# design.net
KiCad netlist of a schematic drawn in EasyEDA
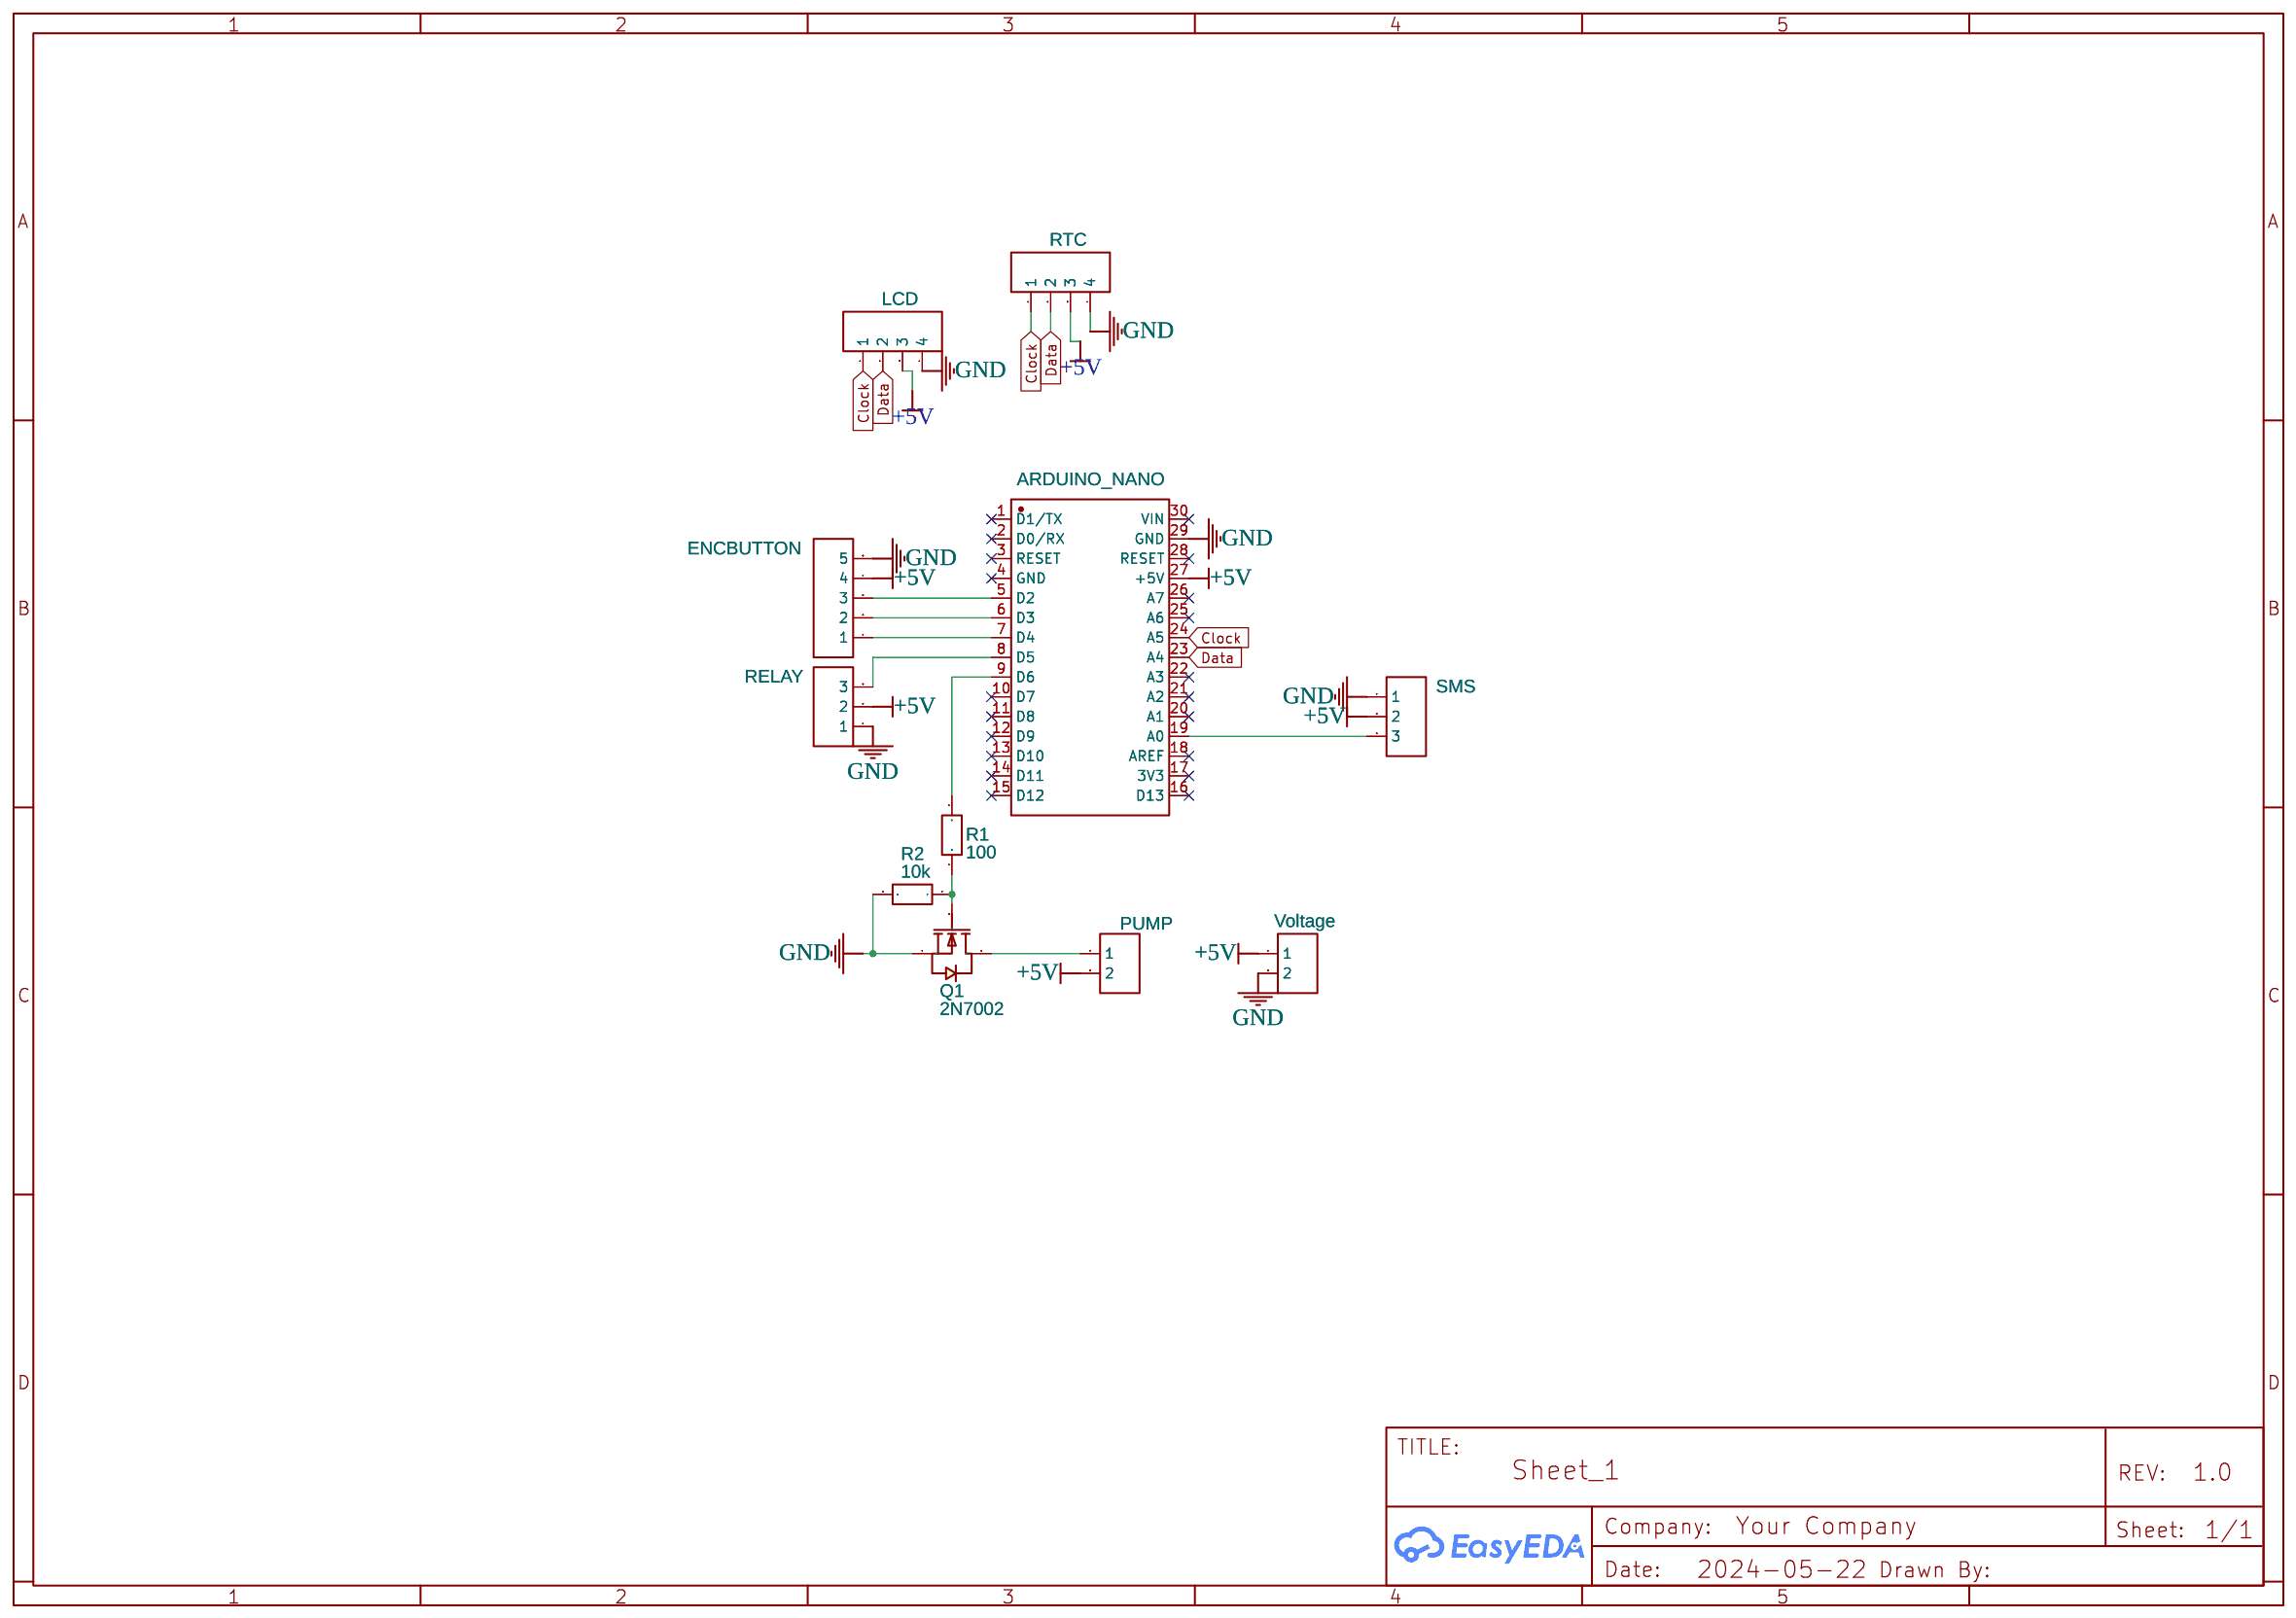
[diagram p0: schematic sheet]

(export (version "E")
  (design (tool "Eeschema 10.0.6"))
  (components
    (comp (ref "ENCBUTTON") (value "HDR-M-2.54_1x5") (libsource (lib "") (part "HDR-M-2.54_1x5")))
    (comp (ref "H1") (value "Voltage") (libsource (lib "") (part "HDR-F-2.54_1x2")))
    (comp (ref "J2") (value "LCD") (libsource (lib "") (part "HDR-M-2.54_1x4")))
    (comp (ref "J3") (value "RTC") (libsource (lib "") (part "HDR-M-2.54_1x4")))
    (comp (ref "PUMP") (value "HDR-M-2.54_1x2") (libsource (lib "") (part "HDR-M-2.54_1x2")))
    (comp (ref "Q1")
      (value "2N7002")
      (fields (field (name "Manufacturer Part") "2N7002,215") (field (name "Manufacturer") "Nexperia"))
      (libsource (lib "") (part "2N7002"))
    )
    (comp (ref "R1") (value "100") (libsource (lib "") (part "R_AXIAL-0.3_EU")))
    (comp (ref "R2") (value "10k") (libsource (lib "") (part "R_AXIAL-0.3_EU_1")))
    (comp (ref "RELAY") (value "HDR-M-2.54_1x3") (libsource (lib "") (part "HDR-M-2.54_1x3_1")))
    (comp (ref "SMS") (value "HDR-M-2.54_1x3") (libsource (lib "") (part "HDR-M-2.54_1x3")))
    (comp (ref "U1") (value "ARDUINO_NANO") (libsource (lib "") (part "ARDUINO_NANO")))
  )
  (nets
    (net (code "1") (name "+5V") (class "Default")
      (node (ref "ENCBUTTON") (pin "4") (pinfunction "4_4") (pintype "unspecified"))
      (node (ref "H1") (pin "1") (pinfunction "1_1") (pintype "input"))
      (node (ref "J2") (pin "3") (pinfunction "3_3") (pintype "unspecified"))
      (node (ref "J3") (pin "3") (pinfunction "3_3") (pintype "unspecified"))
      (node (ref "PUMP") (pin "2") (pinfunction "2_2") (pintype "unspecified"))
      (node (ref "RELAY") (pin "2") (pinfunction "2_2") (pintype "input"))
      (node (ref "SMS") (pin "2") (pinfunction "2_2") (pintype "input"))
      (node (ref "U1") (pin "27") (pinfunction "+5V_27") (pintype "unspecified"))
    )
    (net (code "2") (name "Clock") (class "Default")
      (node (ref "J2") (pin "1") (pinfunction "1_1") (pintype "unspecified"))
      (node (ref "J3") (pin "1") (pinfunction "1_1") (pintype "unspecified"))
      (node (ref "U1") (pin "24") (pinfunction "A5_24") (pintype "unspecified"))
    )
    (net (code "3") (name "Data") (class "Default")
      (node (ref "J2") (pin "2") (pinfunction "2_2") (pintype "unspecified"))
      (node (ref "J3") (pin "2") (pinfunction "2_2") (pintype "unspecified"))
      (node (ref "U1") (pin "23") (pinfunction "A4_23") (pintype "unspecified"))
    )
    (net (code "4") (name "GND") (class "Default")
      (node (ref "ENCBUTTON") (pin "5") (pinfunction "5_5") (pintype "unspecified"))
      (node (ref "H1") (pin "2") (pinfunction "2_2") (pintype "input"))
      (node (ref "J2") (pin "4") (pinfunction "4_4") (pintype "unspecified"))
      (node (ref "J3") (pin "4") (pinfunction "4_4") (pintype "unspecified"))
      (node (ref "Q1") (pin "1") (pinfunction "S_1") (pintype "unspecified"))
      (node (ref "R2") (pin "2") (pinfunction "2_2") (pintype "unspecified"))
      (node (ref "RELAY") (pin "1") (pinfunction "1_1") (pintype "input"))
      (node (ref "SMS") (pin "1") (pinfunction "1_1") (pintype "input"))
      (node (ref "U1") (pin "29") (pinfunction "GND_29") (pintype "unspecified"))
    )
    (net (code "5") (name "Net-(Q1-D)") (class "Default")
      (node (ref "PUMP") (pin "1") (pinfunction "1_1") (pintype "unspecified"))
      (node (ref "Q1") (pin "3") (pinfunction "D_3") (pintype "unspecified"))
    )
    (net (code "6") (name "Net-(Q1-G)") (class "Default")
      (node (ref "Q1") (pin "2") (pinfunction "G_2") (pintype "unspecified"))
      (node (ref "R1") (pin "1") (pinfunction "1_1") (pintype "unspecified"))
      (node (ref "R2") (pin "1") (pinfunction "1_1") (pintype "unspecified"))
    )
    (net (code "7") (name "Net-(U1-A0)") (class "Default")
      (node (ref "SMS") (pin "3") (pinfunction "3_3") (pintype "input"))
      (node (ref "U1") (pin "19") (pinfunction "A0_19") (pintype "unspecified"))
    )
    (net (code "8") (name "Net-(U1-D2)") (class "Default")
      (node (ref "ENCBUTTON") (pin "3") (pinfunction "3_3") (pintype "unspecified"))
      (node (ref "U1") (pin "5") (pinfunction "D2_5") (pintype "unspecified"))
    )
    (net (code "9") (name "Net-(U1-D3)") (class "Default")
      (node (ref "ENCBUTTON") (pin "2") (pinfunction "2_2") (pintype "unspecified"))
      (node (ref "U1") (pin "6") (pinfunction "D3_6") (pintype "unspecified"))
    )
    (net (code "10") (name "Net-(U1-D4)") (class "Default")
      (node (ref "ENCBUTTON") (pin "1") (pinfunction "1_1") (pintype "unspecified"))
      (node (ref "U1") (pin "7") (pinfunction "D4_7") (pintype "unspecified"))
    )
    (net (code "11") (name "Net-(U1-D5)") (class "Default")
      (node (ref "RELAY") (pin "3") (pinfunction "3_3") (pintype "input"))
      (node (ref "U1") (pin "8") (pinfunction "D5_8") (pintype "unspecified"))
    )
    (net (code "12") (name "Net-(U1-D6)") (class "Default")
      (node (ref "R1") (pin "2") (pinfunction "2_2") (pintype "unspecified"))
      (node (ref "U1") (pin "9") (pinfunction "D6_9") (pintype "unspecified"))
    )
    (net (code "13") (name "unconnected-(U1-3V3-Pad17)") (class "Default")
      (node (ref "U1") (pin "17") (pinfunction "3V3_17") (pintype "unspecified+no_connect"))
    )
    (net (code "14") (name "unconnected-(U1-A1-Pad20)") (class "Default")
      (node (ref "U1") (pin "20") (pinfunction "A1_20") (pintype "unspecified+no_connect"))
    )
    (net (code "15") (name "unconnected-(U1-A2-Pad21)") (class "Default")
      (node (ref "U1") (pin "21") (pinfunction "A2_21") (pintype "unspecified+no_connect"))
    )
    (net (code "16") (name "unconnected-(U1-A3-Pad22)") (class "Default")
      (node (ref "U1") (pin "22") (pinfunction "A3_22") (pintype "unspecified+no_connect"))
    )
    (net (code "17") (name "unconnected-(U1-A6-Pad25)") (class "Default")
      (node (ref "U1") (pin "25") (pinfunction "A6_25") (pintype "unspecified+no_connect"))
    )
    (net (code "18") (name "unconnected-(U1-A7-Pad26)") (class "Default")
      (node (ref "U1") (pin "26") (pinfunction "A7_26") (pintype "unspecified+no_connect"))
    )
    (net (code "19") (name "unconnected-(U1-AREF-Pad18)") (class "Default")
      (node (ref "U1") (pin "18") (pinfunction "AREF_18") (pintype "unspecified+no_connect"))
    )
    (net (code "20") (name "unconnected-(U1-D0{slash}RX-Pad2)") (class "Default")
      (node (ref "U1") (pin "2") (pinfunction "D0/RX_2") (pintype "unspecified+no_connect"))
    )
    (net (code "21") (name "unconnected-(U1-D1{slash}TX-Pad1)") (class "Default")
      (node (ref "U1") (pin "1") (pinfunction "D1/TX_1") (pintype "unspecified+no_connect"))
    )
    (net (code "22") (name "unconnected-(U1-D7-Pad10)") (class "Default")
      (node (ref "U1") (pin "10") (pinfunction "D7_10") (pintype "unspecified+no_connect"))
    )
    (net (code "23") (name "unconnected-(U1-D8-Pad11)") (class "Default")
      (node (ref "U1") (pin "11") (pinfunction "D8_11") (pintype "unspecified+no_connect"))
    )
    (net (code "24") (name "unconnected-(U1-D9-Pad12)") (class "Default")
      (node (ref "U1") (pin "12") (pinfunction "D9_12") (pintype "unspecified+no_connect"))
    )
    (net (code "25") (name "unconnected-(U1-D10-Pad13)") (class "Default")
      (node (ref "U1") (pin "13") (pinfunction "D10_13") (pintype "unspecified+no_connect"))
    )
    (net (code "26") (name "unconnected-(U1-D11-Pad14)") (class "Default")
      (node (ref "U1") (pin "14") (pinfunction "D11_14") (pintype "unspecified+no_connect"))
    )
    (net (code "27") (name "unconnected-(U1-D12-Pad15)") (class "Default")
      (node (ref "U1") (pin "15") (pinfunction "D12_15") (pintype "unspecified+no_connect"))
    )
    (net (code "28") (name "unconnected-(U1-D13-Pad16)") (class "Default")
      (node (ref "U1") (pin "16") (pinfunction "D13_16") (pintype "unspecified+no_connect"))
    )
    (net (code "29") (name "unconnected-(U1-GND-Pad4)") (class "Default")
      (node (ref "U1") (pin "4") (pinfunction "GND_4") (pintype "unspecified+no_connect"))
    )
    (net (code "30") (name "unconnected-(U1-RESET-Pad3)") (class "Default")
      (node (ref "U1") (pin "3") (pinfunction "RESET_3") (pintype "unspecified+no_connect"))
    )
    (net (code "31") (name "unconnected-(U1-RESET-Pad28)") (class "Default")
      (node (ref "U1") (pin "28") (pinfunction "RESET_28") (pintype "unspecified+no_connect"))
    )
    (net (code "32") (name "unconnected-(U1-VIN-Pad30)") (class "Default")
      (node (ref "U1") (pin "30") (pinfunction "VIN_30") (pintype "unspecified+no_connect"))
    )
  )
)
